# CapHat.net
KiCad netlist of a schematic drawn in EAGLE
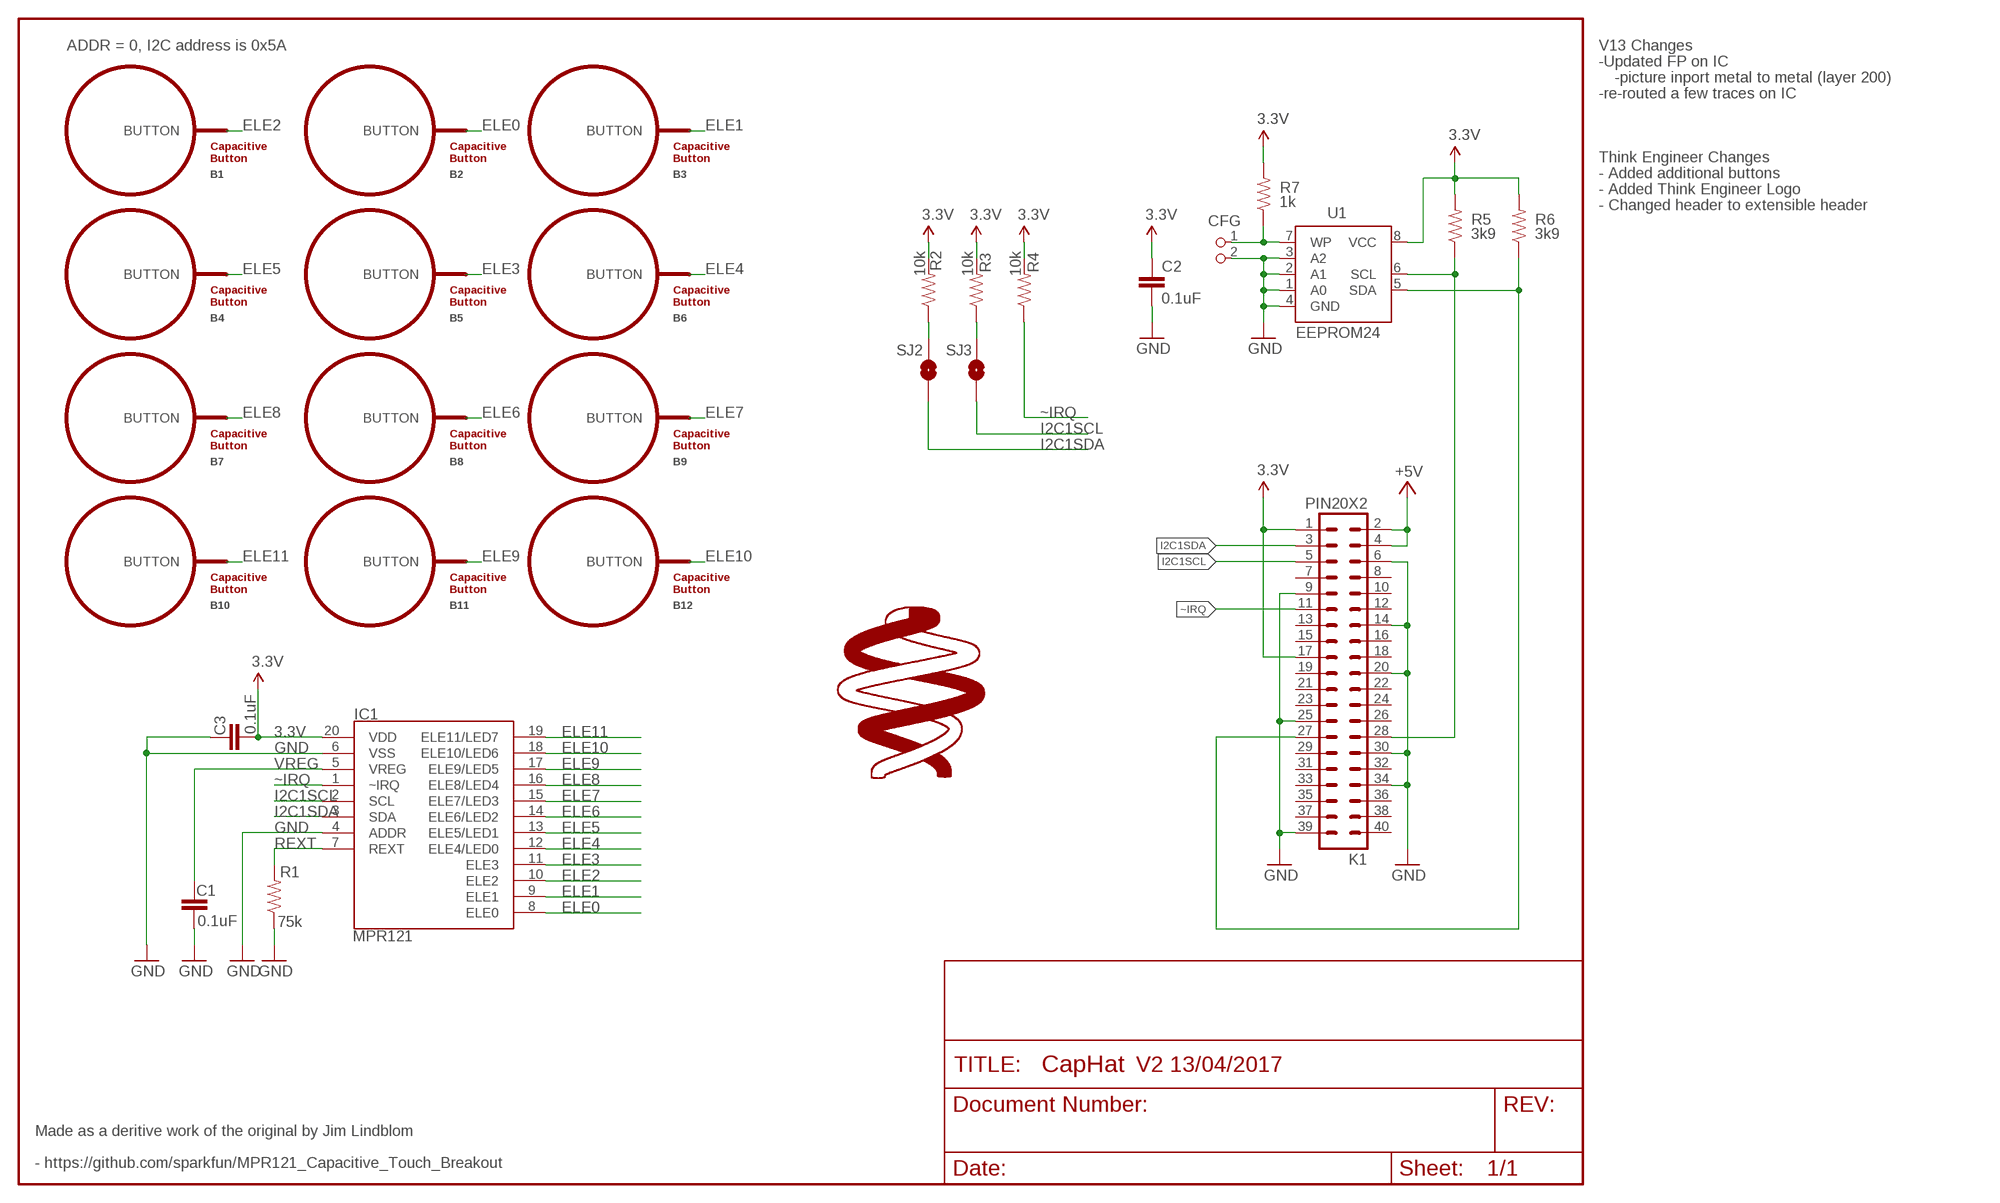
[diagram p0: schematic, sheet 1]

(export (version "E")
  (design (tool "Eeschema 10.0.6"))
  (components
    (comp (ref "B1")
      (value "BUTTON_PASSIVE10MM")
      (footprint "eagle-import:BUTTON_PASSIVE_10MM")
      (libsource (lib "eagle-import") (part "BUTTON_PASSIVE10MM"))
    )
    (comp (ref "B2")
      (value "BUTTON_PASSIVE10MM")
      (footprint "eagle-import:BUTTON_PASSIVE_10MM")
      (libsource (lib "eagle-import") (part "BUTTON_PASSIVE10MM"))
    )
    (comp (ref "B3")
      (value "BUTTON_PASSIVE10MM")
      (footprint "eagle-import:BUTTON_PASSIVE_10MM")
      (libsource (lib "eagle-import") (part "BUTTON_PASSIVE10MM"))
    )
    (comp (ref "B4")
      (value "BUTTON_PASSIVE10MM")
      (footprint "eagle-import:BUTTON_PASSIVE_10MM")
      (libsource (lib "eagle-import") (part "BUTTON_PASSIVE10MM"))
    )
    (comp (ref "B5")
      (value "BUTTON_PASSIVE10MM")
      (footprint "eagle-import:BUTTON_PASSIVE_10MM")
      (libsource (lib "eagle-import") (part "BUTTON_PASSIVE10MM"))
    )
    (comp (ref "B6")
      (value "BUTTON_PASSIVE10MM")
      (footprint "eagle-import:BUTTON_PASSIVE_10MM")
      (libsource (lib "eagle-import") (part "BUTTON_PASSIVE10MM"))
    )
    (comp (ref "B7")
      (value "BUTTON_PASSIVE10MM")
      (footprint "eagle-import:BUTTON_PASSIVE_10MM")
      (libsource (lib "eagle-import") (part "BUTTON_PASSIVE10MM"))
    )
    (comp (ref "B8")
      (value "BUTTON_PASSIVE10MM")
      (footprint "eagle-import:BUTTON_PASSIVE_10MM")
      (libsource (lib "eagle-import") (part "BUTTON_PASSIVE10MM"))
    )
    (comp (ref "B9")
      (value "BUTTON_PASSIVE10MM")
      (footprint "eagle-import:BUTTON_PASSIVE_10MM")
      (libsource (lib "eagle-import") (part "BUTTON_PASSIVE10MM"))
    )
    (comp (ref "B10")
      (value "BUTTON_PASSIVE10MM")
      (footprint "eagle-import:BUTTON_PASSIVE_10MM")
      (libsource (lib "eagle-import") (part "BUTTON_PASSIVE10MM"))
    )
    (comp (ref "B11")
      (value "BUTTON_PASSIVE10MM")
      (footprint "eagle-import:BUTTON_PASSIVE_10MM")
      (libsource (lib "eagle-import") (part "BUTTON_PASSIVE10MM"))
    )
    (comp (ref "B12")
      (value "BUTTON_PASSIVE10MM")
      (footprint "eagle-import:BUTTON_PASSIVE_10MM")
      (libsource (lib "eagle-import") (part "BUTTON_PASSIVE10MM"))
    )
    (comp (ref "C1")
      (value "0.1uF")
      (footprint "eagle-import:0603-CAP")
      (libsource (lib "eagle-import") (part "CAP0603-CAP"))
    )
    (comp (ref "C2")
      (value "0.1uF")
      (footprint "eagle-import:0603-CAP")
      (libsource (lib "eagle-import") (part "CAP0603-CAP"))
    )
    (comp (ref "C3")
      (value "0.1uF")
      (footprint "eagle-import:0603-CAP")
      (libsource (lib "eagle-import") (part "CAP0603-CAP"))
    )
    (comp (ref "CFG")
      (value "PIN2_100")
      (footprint "eagle-import:PIN_W_2")
      (libsource (lib "eagle-import") (part "PIN2_100"))
    )
    (comp (ref "IC1")
      (value "MPR121")
      (footprint "eagle-import:QFN-20-0.4MM-V2")
      (libsource (lib "eagle-import") (part "MPR121V2"))
    )
    (comp (ref "K1")
      (value "PIN20X2")
      (footprint "eagle-import:PIN_20X2")
      (libsource (lib "eagle-import") (part "PIN20X2"))
    )
    (comp (ref "R1")
      (value "75k")
      (footprint "eagle-import:0603-RES")
      (libsource (lib "eagle-import") (part "SparkFun-Resistors_RESISTOR0603-RES"))
    )
    (comp (ref "R2")
      (value "10k")
      (footprint "eagle-import:0603-RES")
      (libsource (lib "eagle-import") (part "RESISTOR0603-RES"))
    )
    (comp (ref "R3")
      (value "10k")
      (footprint "eagle-import:0603-RES")
      (libsource (lib "eagle-import") (part "RESISTOR0603-RES"))
    )
    (comp (ref "R4")
      (value "10k")
      (footprint "eagle-import:0603-RES")
      (libsource (lib "eagle-import") (part "RESISTOR0603-RES"))
    )
    (comp (ref "R5")
      (value "3k9")
      (footprint "eagle-import:0603-RES")
      (fields (field (name "TOLERANCE") "5%"))
      (libsource (lib "eagle-import") (part "SparkFun-Resistors_RESISTOR0603-RES"))
    )
    (comp (ref "R6")
      (value "3k9")
      (footprint "eagle-import:0603-RES")
      (fields (field (name "TOLERANCE") "5%"))
      (libsource (lib "eagle-import") (part "SparkFun-Resistors_RESISTOR0603-RES"))
    )
    (comp (ref "R7")
      (value "1k")
      (footprint "eagle-import:0603-RES")
      (fields (field (name "TOLERANCE") "5%"))
      (libsource (lib "eagle-import") (part "SparkFun-Resistors_RESISTOR0603-RES"))
    )
    (comp (ref "SJ2")
      (value "SOLDERJUMPERNO")
      (footprint "eagle-import:SJ_2S-NO")
      (libsource (lib "eagle-import") (part "SOLDERJUMPERNO"))
    )
    (comp (ref "SJ3")
      (value "SOLDERJUMPERNO")
      (footprint "eagle-import:SJ_2S-NO")
      (libsource (lib "eagle-import") (part "SOLDERJUMPERNO"))
    )
    (comp (ref "U$1")
      (value "THINK_LOGO")
      (footprint "eagle-import:THINK_LOGO")
      (libsource (lib "eagle-import") (part "THINK_LOGO"))
    )
    (comp (ref "U1")
      (value "EEPROM24")
      (footprint "eagle-import:SOIC8")
      (libsource (lib "eagle-import") (part "EEPROM24"))
    )
  )
  (nets
    (net (code "1") (name "+5V") (class "Default")
      (node (ref "K1") (pin "2") (pinfunction "2_2") (pintype "passive"))
      (node (ref "K1") (pin "4") (pinfunction "4_4") (pintype "passive"))
    )
    (net (code "2") (name "/ELE0") (class "Default")
      (node (ref "B2") (pin "BUTTON") (pinfunction "BUTTON_BUTTON") (pintype "passive"))
      (node (ref "IC1") (pin "8") (pinfunction "ELE0_8") (pintype "bidirectional"))
    )
    (net (code "3") (name "/ELE1") (class "Default")
      (node (ref "B3") (pin "BUTTON") (pinfunction "BUTTON_BUTTON") (pintype "passive"))
      (node (ref "IC1") (pin "9") (pinfunction "ELE1_9") (pintype "bidirectional"))
    )
    (net (code "4") (name "/ELE2") (class "Default")
      (node (ref "B1") (pin "BUTTON") (pinfunction "BUTTON_BUTTON") (pintype "passive"))
      (node (ref "IC1") (pin "10") (pinfunction "ELE2_10") (pintype "bidirectional"))
    )
    (net (code "5") (name "/ELE3") (class "Default")
      (node (ref "B5") (pin "BUTTON") (pinfunction "BUTTON_BUTTON") (pintype "passive"))
      (node (ref "IC1") (pin "11") (pinfunction "ELE3_11") (pintype "bidirectional"))
    )
    (net (code "6") (name "/ELE4") (class "Default")
      (node (ref "B6") (pin "BUTTON") (pinfunction "BUTTON_BUTTON") (pintype "passive"))
      (node (ref "IC1") (pin "12") (pinfunction "ELE4/LED0_12") (pintype "bidirectional"))
    )
    (net (code "7") (name "/ELE5") (class "Default")
      (node (ref "B4") (pin "BUTTON") (pinfunction "BUTTON_BUTTON") (pintype "passive"))
      (node (ref "IC1") (pin "13") (pinfunction "ELE5/LED1_13") (pintype "bidirectional"))
    )
    (net (code "8") (name "/ELE6") (class "Default")
      (node (ref "B8") (pin "BUTTON") (pinfunction "BUTTON_BUTTON") (pintype "passive"))
      (node (ref "IC1") (pin "14") (pinfunction "ELE6/LED2_14") (pintype "bidirectional"))
    )
    (net (code "9") (name "/ELE7") (class "Default")
      (node (ref "B9") (pin "BUTTON") (pinfunction "BUTTON_BUTTON") (pintype "passive"))
      (node (ref "IC1") (pin "15") (pinfunction "ELE7/LED3_15") (pintype "bidirectional"))
    )
    (net (code "10") (name "/ELE8") (class "Default")
      (node (ref "B7") (pin "BUTTON") (pinfunction "BUTTON_BUTTON") (pintype "passive"))
      (node (ref "IC1") (pin "16") (pinfunction "ELE8/LED4_16") (pintype "bidirectional"))
    )
    (net (code "11") (name "/ELE9") (class "Default")
      (node (ref "B11") (pin "BUTTON") (pinfunction "BUTTON_BUTTON") (pintype "passive"))
      (node (ref "IC1") (pin "17") (pinfunction "ELE9/LED5_17") (pintype "bidirectional"))
    )
    (net (code "12") (name "/ELE10") (class "Default")
      (node (ref "B12") (pin "BUTTON") (pinfunction "BUTTON_BUTTON") (pintype "passive"))
      (node (ref "IC1") (pin "18") (pinfunction "ELE10/LED6_18") (pintype "bidirectional"))
    )
    (net (code "13") (name "/ELE11") (class "Default")
      (node (ref "B10") (pin "BUTTON") (pinfunction "BUTTON_BUTTON") (pintype "passive"))
      (node (ref "IC1") (pin "19") (pinfunction "ELE11/LED7_19") (pintype "bidirectional"))
    )
    (net (code "14") (name "/REXT") (class "Default")
      (node (ref "IC1") (pin "7") (pinfunction "REXT_7") (pintype "bidirectional"))
      (node (ref "R1") (pin "2") (pinfunction "2_2") (pintype "passive"))
    )
    (net (code "15") (name "/VREG") (class "Default")
      (node (ref "C1") (pin "1") (pinfunction "1_1") (pintype "passive"))
      (node (ref "IC1") (pin "5") (pinfunction "VREG_5") (pintype "bidirectional"))
    )
    (net (code "16") (name "/~{IRQ}") (class "Default")
      (node (ref "IC1") (pin "1") (pinfunction "~{IRQ}_1") (pintype "bidirectional"))
      (node (ref "K1") (pin "11") (pinfunction "11_11") (pintype "passive"))
      (node (ref "R4") (pin "1") (pinfunction "1_1") (pintype "passive"))
    )
    (net (code "17") (name "3.3V") (class "Default")
      (node (ref "C2") (pin "1") (pinfunction "1_1") (pintype "passive"))
      (node (ref "C3") (pin "2") (pinfunction "2_2") (pintype "passive"))
      (node (ref "IC1") (pin "20") (pinfunction "VDD_20") (pintype "bidirectional"))
      (node (ref "K1") (pin "1") (pinfunction "1_1") (pintype "passive"))
      (node (ref "K1") (pin "17") (pinfunction "17_17") (pintype "passive"))
      (node (ref "R2") (pin "2") (pinfunction "2_2") (pintype "passive"))
      (node (ref "R3") (pin "2") (pinfunction "2_2") (pintype "passive"))
      (node (ref "R4") (pin "2") (pinfunction "2_2") (pintype "passive"))
      (node (ref "R5") (pin "2") (pinfunction "2_2") (pintype "passive"))
      (node (ref "R6") (pin "2") (pinfunction "2_2") (pintype "passive"))
      (node (ref "R7") (pin "2") (pinfunction "2_2") (pintype "passive"))
      (node (ref "U1") (pin "8") (pinfunction "VCC_8") (pintype "power_in"))
    )
    (net (code "18") (name "GND") (class "Default")
      (node (ref "C1") (pin "2") (pinfunction "2_2") (pintype "passive"))
      (node (ref "C2") (pin "2") (pinfunction "2_2") (pintype "passive"))
      (node (ref "C3") (pin "1") (pinfunction "1_1") (pintype "passive"))
      (node (ref "CFG") (pin "2") (pinfunction "2_2") (pintype "passive"))
      (node (ref "IC1") (pin "4") (pinfunction "ADDR_4") (pintype "bidirectional"))
      (node (ref "IC1") (pin "6") (pinfunction "VSS_6") (pintype "bidirectional"))
      (node (ref "K1") (pin "14") (pinfunction "14_14") (pintype "passive"))
      (node (ref "K1") (pin "20") (pinfunction "20_20") (pintype "passive"))
      (node (ref "K1") (pin "25") (pinfunction "25_25") (pintype "passive"))
      (node (ref "K1") (pin "30") (pinfunction "30_30") (pintype "passive"))
      (node (ref "K1") (pin "34") (pinfunction "34_34") (pintype "passive"))
      (node (ref "K1") (pin "39") (pinfunction "39_39") (pintype "passive"))
      (node (ref "K1") (pin "6") (pinfunction "6_6") (pintype "passive"))
      (node (ref "K1") (pin "9") (pinfunction "9_9") (pintype "passive"))
      (node (ref "R1") (pin "1") (pinfunction "1_1") (pintype "passive"))
      (node (ref "U1") (pin "1") (pinfunction "A0_1") (pintype "input"))
      (node (ref "U1") (pin "2") (pinfunction "A1_2") (pintype "input"))
      (node (ref "U1") (pin "3") (pinfunction "A2_3") (pintype "input"))
      (node (ref "U1") (pin "4") (pinfunction "GND_4") (pintype "power_in"))
    )
    (net (code "19") (name "I2C1SCL") (class "Default")
      (node (ref "IC1") (pin "2") (pinfunction "SCL_2") (pintype "bidirectional"))
      (node (ref "K1") (pin "5") (pinfunction "5_5") (pintype "passive"))
      (node (ref "SJ3") (pin "1") (pinfunction "1_1") (pintype "passive"))
    )
    (net (code "20") (name "I2C1SDA") (class "Default")
      (node (ref "IC1") (pin "3") (pinfunction "SDA_3") (pintype "bidirectional"))
      (node (ref "K1") (pin "3") (pinfunction "3_3") (pintype "passive"))
      (node (ref "SJ2") (pin "1") (pinfunction "1_1") (pintype "passive"))
    )
    (net (code "21") (name "Net-(R2-Pad1)") (class "Default")
      (node (ref "R2") (pin "1") (pinfunction "1_1") (pintype "passive"))
      (node (ref "SJ2") (pin "2") (pinfunction "2_2") (pintype "passive"))
    )
    (net (code "22") (name "Net-(R3-Pad1)") (class "Default")
      (node (ref "R3") (pin "1") (pinfunction "1_1") (pintype "passive"))
      (node (ref "SJ3") (pin "2") (pinfunction "2_2") (pintype "passive"))
    )
    (net (code "23") (name "Net-(U1-SCL)") (class "Default")
      (node (ref "K1") (pin "28") (pinfunction "28_28") (pintype "passive"))
      (node (ref "R5") (pin "1") (pinfunction "1_1") (pintype "passive"))
      (node (ref "U1") (pin "6") (pinfunction "SCL_6") (pintype "input"))
    )
    (net (code "24") (name "Net-(U1-SDA)") (class "Default")
      (node (ref "K1") (pin "27") (pinfunction "27_27") (pintype "passive"))
      (node (ref "R6") (pin "1") (pinfunction "1_1") (pintype "passive"))
      (node (ref "U1") (pin "5") (pinfunction "SDA_5") (pintype "bidirectional"))
    )
    (net (code "25") (name "Net-(U1-WP)") (class "Default")
      (node (ref "CFG") (pin "1") (pinfunction "1_1") (pintype "passive"))
      (node (ref "R7") (pin "1") (pinfunction "1_1") (pintype "passive"))
      (node (ref "U1") (pin "7") (pinfunction "WP_7") (pintype "input"))
    )
    (net (code "26") (name "unconnected-(K1-Pad7)") (class "Default")
      (node (ref "K1") (pin "7") (pinfunction "7_7") (pintype "passive"))
    )
    (net (code "27") (name "unconnected-(K1-Pad8)") (class "Default")
      (node (ref "K1") (pin "8") (pinfunction "8_8") (pintype "passive"))
    )
    (net (code "28") (name "unconnected-(K1-Pad10)") (class "Default")
      (node (ref "K1") (pin "10") (pinfunction "10_10") (pintype "passive"))
    )
    (net (code "29") (name "unconnected-(K1-Pad12)") (class "Default")
      (node (ref "K1") (pin "12") (pinfunction "12_12") (pintype "passive"))
    )
    (net (code "30") (name "unconnected-(K1-Pad13)") (class "Default")
      (node (ref "K1") (pin "13") (pinfunction "13_13") (pintype "passive"))
    )
    (net (code "31") (name "unconnected-(K1-Pad15)") (class "Default")
      (node (ref "K1") (pin "15") (pinfunction "15_15") (pintype "passive"))
    )
    (net (code "32") (name "unconnected-(K1-Pad16)") (class "Default")
      (node (ref "K1") (pin "16") (pinfunction "16_16") (pintype "passive"))
    )
    (net (code "33") (name "unconnected-(K1-Pad18)") (class "Default")
      (node (ref "K1") (pin "18") (pinfunction "18_18") (pintype "passive"))
    )
    (net (code "34") (name "unconnected-(K1-Pad19)") (class "Default")
      (node (ref "K1") (pin "19") (pinfunction "19_19") (pintype "passive"))
    )
    (net (code "35") (name "unconnected-(K1-Pad21)") (class "Default")
      (node (ref "K1") (pin "21") (pinfunction "21_21") (pintype "passive"))
    )
    (net (code "36") (name "unconnected-(K1-Pad22)") (class "Default")
      (node (ref "K1") (pin "22") (pinfunction "22_22") (pintype "passive"))
    )
    (net (code "37") (name "unconnected-(K1-Pad23)") (class "Default")
      (node (ref "K1") (pin "23") (pinfunction "23_23") (pintype "passive"))
    )
    (net (code "38") (name "unconnected-(K1-Pad24)") (class "Default")
      (node (ref "K1") (pin "24") (pinfunction "24_24") (pintype "passive"))
    )
    (net (code "39") (name "unconnected-(K1-Pad26)") (class "Default")
      (node (ref "K1") (pin "26") (pinfunction "26_26") (pintype "passive"))
    )
    (net (code "40") (name "unconnected-(K1-Pad29)") (class "Default")
      (node (ref "K1") (pin "29") (pinfunction "29_29") (pintype "passive"))
    )
    (net (code "41") (name "unconnected-(K1-Pad31)") (class "Default")
      (node (ref "K1") (pin "31") (pinfunction "31_31") (pintype "passive"))
    )
    (net (code "42") (name "unconnected-(K1-Pad32)") (class "Default")
      (node (ref "K1") (pin "32") (pinfunction "32_32") (pintype "passive"))
    )
    (net (code "43") (name "unconnected-(K1-Pad33)") (class "Default")
      (node (ref "K1") (pin "33") (pinfunction "33_33") (pintype "passive"))
    )
    (net (code "44") (name "unconnected-(K1-Pad35)") (class "Default")
      (node (ref "K1") (pin "35") (pinfunction "35_35") (pintype "passive"))
    )
    (net (code "45") (name "unconnected-(K1-Pad36)") (class "Default")
      (node (ref "K1") (pin "36") (pinfunction "36_36") (pintype "passive"))
    )
    (net (code "46") (name "unconnected-(K1-Pad37)") (class "Default")
      (node (ref "K1") (pin "37") (pinfunction "37_37") (pintype "passive"))
    )
    (net (code "47") (name "unconnected-(K1-Pad38)") (class "Default")
      (node (ref "K1") (pin "38") (pinfunction "38_38") (pintype "passive"))
    )
    (net (code "48") (name "unconnected-(K1-Pad40)") (class "Default")
      (node (ref "K1") (pin "40") (pinfunction "40_40") (pintype "passive"))
    )
  )
)
